# illuminator_bar.net
KiCad netlist of a schematic drawn in EAGLE
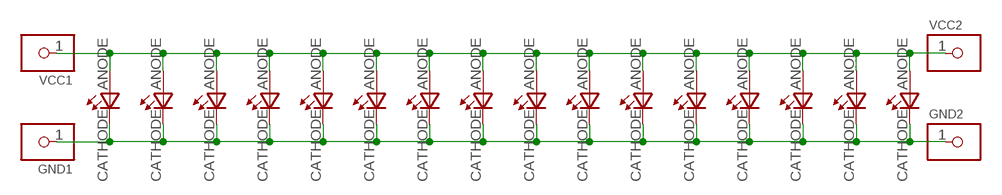
[diagram p0: schematic, sheet 1]

(export (version "E")
  (design (tool "Eeschema 10.0.6"))
  (components
    (comp (ref "GND1")
      (value "1X0108L")
      (footprint "eagle-import:1X01_0.8_UNSIGNED_LONG")
      (libsource (lib "eagle-import") (part "1X0108L"))
    )
    (comp (ref "GND2")
      (value "1X0108L")
      (footprint "eagle-import:1X01_0.8_UNSIGNED_LONG")
      (libsource (lib "eagle-import") (part "1X0108L"))
    )
    (comp (ref "U$1")
      (value "NSCB100")
      (footprint "eagle-import:NSCB100")
      (libsource (lib "eagle-import") (part "NSCB100"))
    )
    (comp (ref "U$2")
      (value "NSCB100")
      (footprint "eagle-import:NSCB100")
      (libsource (lib "eagle-import") (part "NSCB100"))
    )
    (comp (ref "U$3")
      (value "NSCB100")
      (footprint "eagle-import:NSCB100")
      (libsource (lib "eagle-import") (part "NSCB100"))
    )
    (comp (ref "U$4")
      (value "NSCB100")
      (footprint "eagle-import:NSCB100")
      (libsource (lib "eagle-import") (part "NSCB100"))
    )
    (comp (ref "U$5")
      (value "NSCB100")
      (footprint "eagle-import:NSCB100")
      (libsource (lib "eagle-import") (part "NSCB100"))
    )
    (comp (ref "U$6")
      (value "NSCB100")
      (footprint "eagle-import:NSCB100")
      (libsource (lib "eagle-import") (part "NSCB100"))
    )
    (comp (ref "U$7")
      (value "NSCB100")
      (footprint "eagle-import:NSCB100")
      (libsource (lib "eagle-import") (part "NSCB100"))
    )
    (comp (ref "U$8")
      (value "NSCB100")
      (footprint "eagle-import:NSCB100")
      (libsource (lib "eagle-import") (part "NSCB100"))
    )
    (comp (ref "U$9")
      (value "NSCB100")
      (footprint "eagle-import:NSCB100")
      (libsource (lib "eagle-import") (part "NSCB100"))
    )
    (comp (ref "U$10")
      (value "NSCB100")
      (footprint "eagle-import:NSCB100")
      (libsource (lib "eagle-import") (part "NSCB100"))
    )
    (comp (ref "U$11")
      (value "NSCB100")
      (footprint "eagle-import:NSCB100")
      (libsource (lib "eagle-import") (part "NSCB100"))
    )
    (comp (ref "U$12")
      (value "NSCB100")
      (footprint "eagle-import:NSCB100")
      (libsource (lib "eagle-import") (part "NSCB100"))
    )
    (comp (ref "U$13")
      (value "NSCB100")
      (footprint "eagle-import:NSCB100")
      (libsource (lib "eagle-import") (part "NSCB100"))
    )
    (comp (ref "U$14")
      (value "NSCB100")
      (footprint "eagle-import:NSCB100")
      (libsource (lib "eagle-import") (part "NSCB100"))
    )
    (comp (ref "U$15")
      (value "NSCB100")
      (footprint "eagle-import:NSCB100")
      (libsource (lib "eagle-import") (part "NSCB100"))
    )
    (comp (ref "U$16")
      (value "NSCB100")
      (footprint "eagle-import:NSCB100")
      (libsource (lib "eagle-import") (part "NSCB100"))
    )
    (comp (ref "VCC1")
      (value "1X0108L")
      (footprint "eagle-import:1X01_0.8_UNSIGNED_LONG")
      (libsource (lib "eagle-import") (part "1X0108L"))
    )
    (comp (ref "VCC2")
      (value "1X0108L")
      (footprint "eagle-import:1X01_0.8_UNSIGNED_LONG")
      (libsource (lib "eagle-import") (part "1X0108L"))
    )
  )
  (nets
    (net (code "1") (name "Net-(U$1-A)") (class "Default")
      (node (ref "U$1") (pin "ANODE") (pinfunction "A_ANODE") (pintype "passive"))
      (node (ref "U$10") (pin "ANODE") (pinfunction "A_ANODE") (pintype "passive"))
      (node (ref "U$11") (pin "ANODE") (pinfunction "A_ANODE") (pintype "passive"))
      (node (ref "U$12") (pin "ANODE") (pinfunction "A_ANODE") (pintype "passive"))
      (node (ref "U$13") (pin "ANODE") (pinfunction "A_ANODE") (pintype "passive"))
      (node (ref "U$14") (pin "ANODE") (pinfunction "A_ANODE") (pintype "passive"))
      (node (ref "U$15") (pin "ANODE") (pinfunction "A_ANODE") (pintype "passive"))
      (node (ref "U$16") (pin "ANODE") (pinfunction "A_ANODE") (pintype "passive"))
      (node (ref "U$2") (pin "ANODE") (pinfunction "A_ANODE") (pintype "passive"))
      (node (ref "U$3") (pin "ANODE") (pinfunction "A_ANODE") (pintype "passive"))
      (node (ref "U$4") (pin "ANODE") (pinfunction "A_ANODE") (pintype "passive"))
      (node (ref "U$5") (pin "ANODE") (pinfunction "A_ANODE") (pintype "passive"))
      (node (ref "U$6") (pin "ANODE") (pinfunction "A_ANODE") (pintype "passive"))
      (node (ref "U$7") (pin "ANODE") (pinfunction "A_ANODE") (pintype "passive"))
      (node (ref "U$8") (pin "ANODE") (pinfunction "A_ANODE") (pintype "passive"))
      (node (ref "U$9") (pin "ANODE") (pinfunction "A_ANODE") (pintype "passive"))
      (node (ref "VCC1") (pin "1") (pinfunction "1_1") (pintype "passive"))
      (node (ref "VCC2") (pin "1") (pinfunction "1_1") (pintype "passive"))
    )
    (net (code "2") (name "Net-(U$1-C)") (class "Default")
      (node (ref "GND1") (pin "1") (pinfunction "1_1") (pintype "passive"))
      (node (ref "GND2") (pin "1") (pinfunction "1_1") (pintype "passive"))
      (node (ref "U$1") (pin "CATHODE") (pinfunction "C_CATHODE") (pintype "passive"))
      (node (ref "U$10") (pin "CATHODE") (pinfunction "C_CATHODE") (pintype "passive"))
      (node (ref "U$11") (pin "CATHODE") (pinfunction "C_CATHODE") (pintype "passive"))
      (node (ref "U$12") (pin "CATHODE") (pinfunction "C_CATHODE") (pintype "passive"))
      (node (ref "U$13") (pin "CATHODE") (pinfunction "C_CATHODE") (pintype "passive"))
      (node (ref "U$14") (pin "CATHODE") (pinfunction "C_CATHODE") (pintype "passive"))
      (node (ref "U$15") (pin "CATHODE") (pinfunction "C_CATHODE") (pintype "passive"))
      (node (ref "U$16") (pin "CATHODE") (pinfunction "C_CATHODE") (pintype "passive"))
      (node (ref "U$2") (pin "CATHODE") (pinfunction "C_CATHODE") (pintype "passive"))
      (node (ref "U$3") (pin "CATHODE") (pinfunction "C_CATHODE") (pintype "passive"))
      (node (ref "U$4") (pin "CATHODE") (pinfunction "C_CATHODE") (pintype "passive"))
      (node (ref "U$5") (pin "CATHODE") (pinfunction "C_CATHODE") (pintype "passive"))
      (node (ref "U$6") (pin "CATHODE") (pinfunction "C_CATHODE") (pintype "passive"))
      (node (ref "U$7") (pin "CATHODE") (pinfunction "C_CATHODE") (pintype "passive"))
      (node (ref "U$8") (pin "CATHODE") (pinfunction "C_CATHODE") (pintype "passive"))
      (node (ref "U$9") (pin "CATHODE") (pinfunction "C_CATHODE") (pintype "passive"))
    )
  )
)
